# M506C.net
KiCad netlist of a schematic drawn in EAGLE
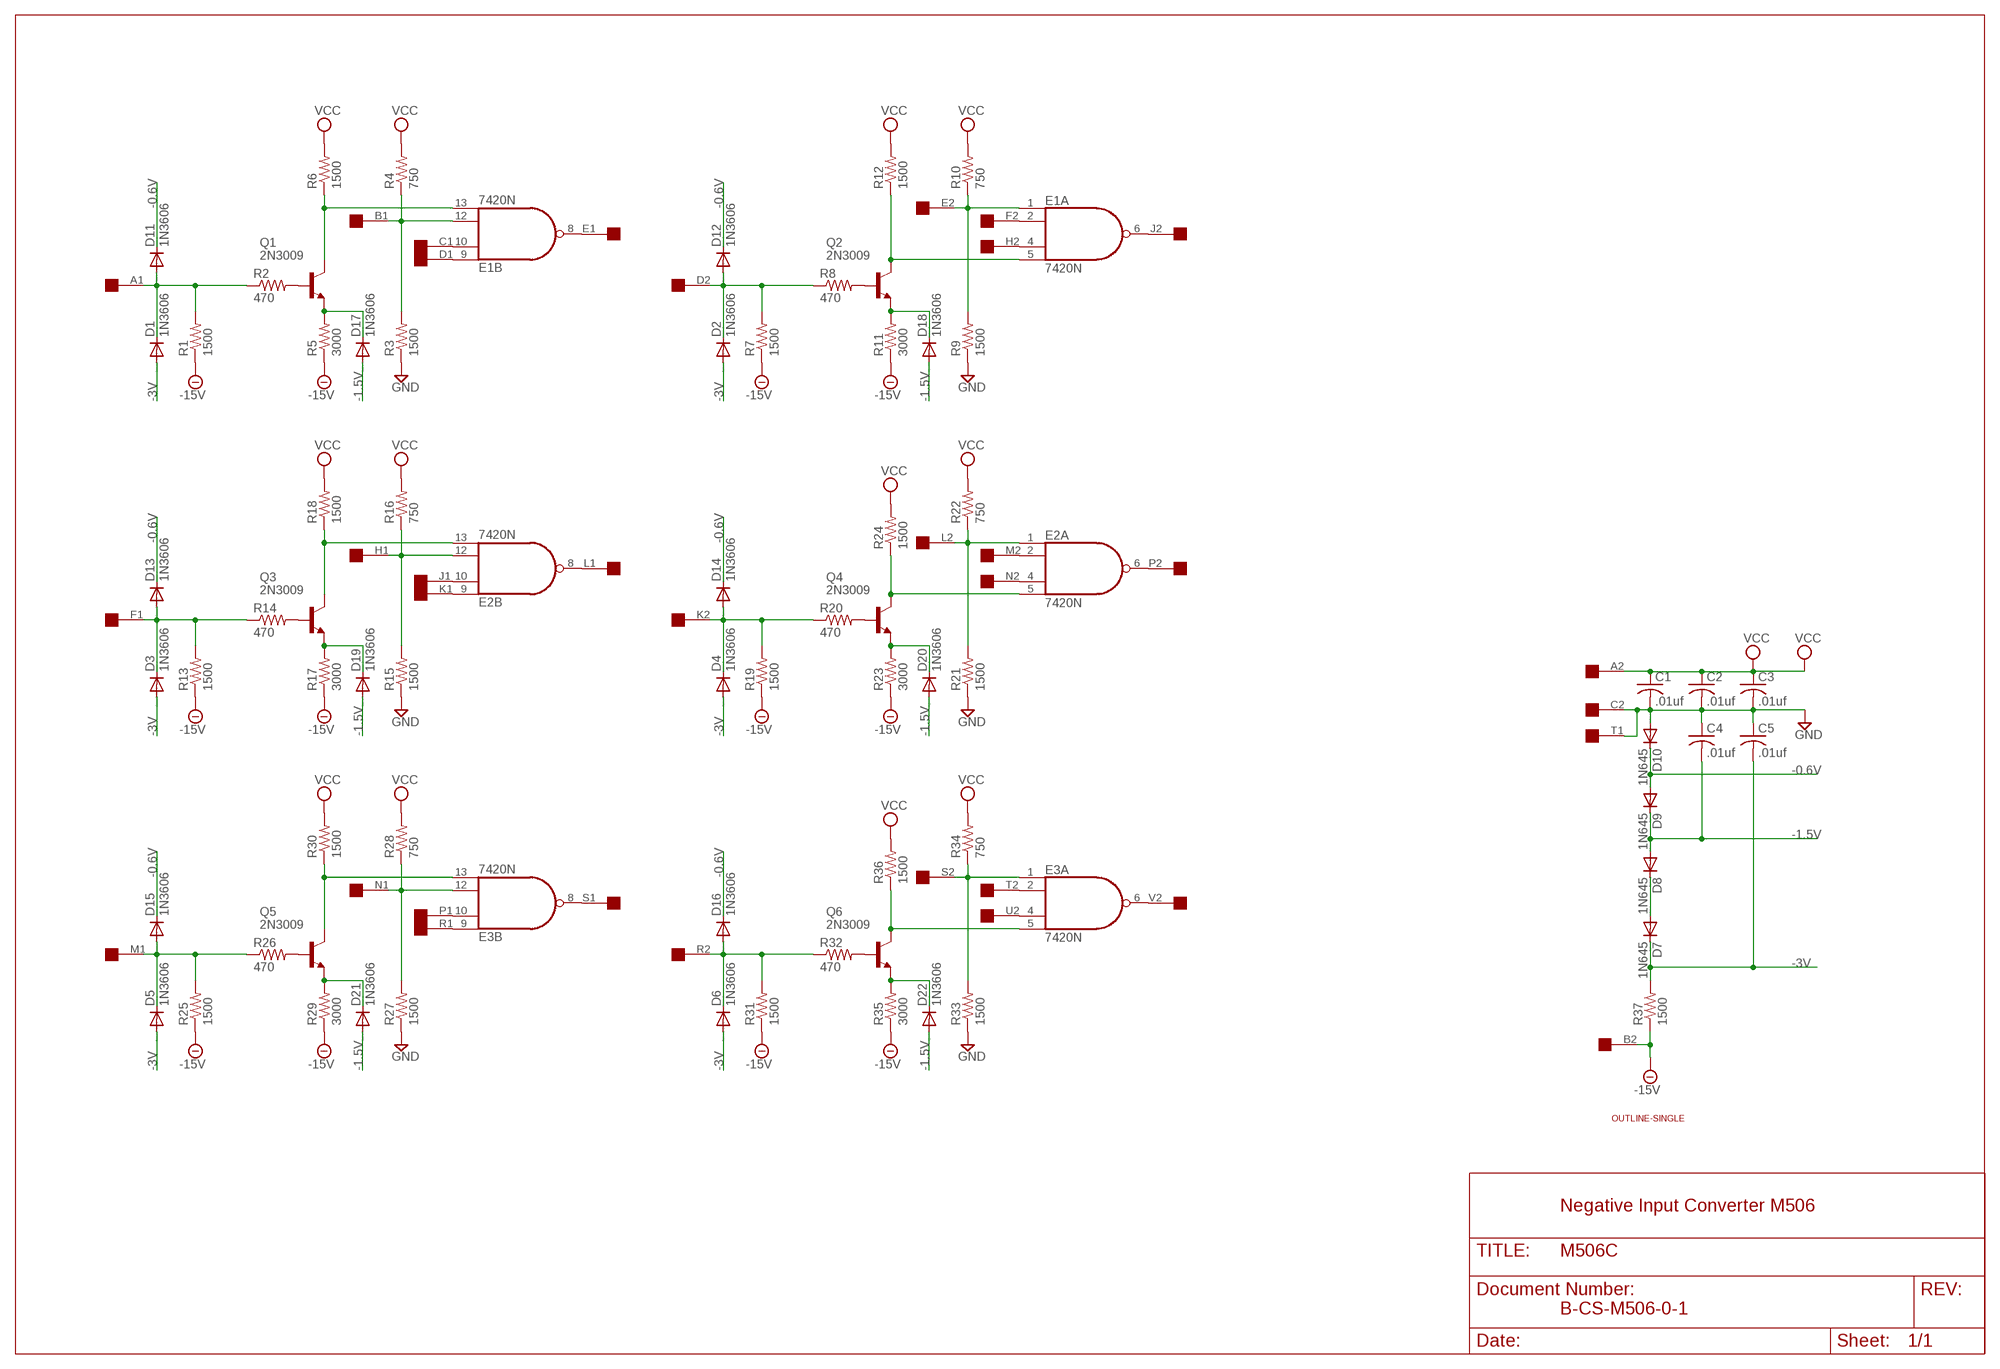
[diagram p0: schematic, sheet 1]

(export (version "E")
  (design (tool "Eeschema 10.0.6"))
  (components
    (comp (ref "C1")
      (value ".01uf")
      (footprint "eagle-import:C050-025X075")
      (libsource (lib "eagle-import") (part "C-US050-025X075"))
    )
    (comp (ref "C2")
      (value ".01uf")
      (footprint "eagle-import:C050-025X075")
      (libsource (lib "eagle-import") (part "C-US050-025X075"))
    )
    (comp (ref "C3")
      (value ".01uf")
      (footprint "eagle-import:C050-025X075")
      (libsource (lib "eagle-import") (part "C-US050-025X075"))
    )
    (comp (ref "C4")
      (value ".01uf")
      (footprint "eagle-import:C050-025X075")
      (libsource (lib "eagle-import") (part "C-US050-025X075"))
    )
    (comp (ref "C5")
      (value ".01uf")
      (footprint "eagle-import:C050-025X075")
      (libsource (lib "eagle-import") (part "C-US050-025X075"))
    )
    (comp (ref "D1")
      (value "1N3606")
      (footprint "eagle-import:DO35-10")
      (libsource (lib "eagle-import") (part "1N4148DO35-10"))
    )
    (comp (ref "D2")
      (value "1N3606")
      (footprint "eagle-import:DO35-10")
      (libsource (lib "eagle-import") (part "1N4148DO35-10"))
    )
    (comp (ref "D3")
      (value "1N3606")
      (footprint "eagle-import:DO35-10")
      (libsource (lib "eagle-import") (part "1N4148DO35-10"))
    )
    (comp (ref "D4")
      (value "1N3606")
      (footprint "eagle-import:DO35-10")
      (libsource (lib "eagle-import") (part "1N4148DO35-10"))
    )
    (comp (ref "D5")
      (value "1N3606")
      (footprint "eagle-import:DO35-10")
      (libsource (lib "eagle-import") (part "1N4148DO35-10"))
    )
    (comp (ref "D6")
      (value "1N3606")
      (footprint "eagle-import:DO35-10")
      (libsource (lib "eagle-import") (part "1N4148DO35-10"))
    )
    (comp (ref "D7")
      (value "1N645")
      (footprint "eagle-import:DO35-10")
      (libsource (lib "eagle-import") (part "1N4148DO35-10"))
    )
    (comp (ref "D8")
      (value "1N645")
      (footprint "eagle-import:DO35-10")
      (libsource (lib "eagle-import") (part "1N4148DO35-10"))
    )
    (comp (ref "D9")
      (value "1N645")
      (footprint "eagle-import:DO35-10")
      (libsource (lib "eagle-import") (part "1N4148DO35-10"))
    )
    (comp (ref "D10")
      (value "1N645")
      (footprint "eagle-import:DO35-10")
      (libsource (lib "eagle-import") (part "1N4148DO35-10"))
    )
    (comp (ref "D11")
      (value "1N3606")
      (footprint "eagle-import:DO35-10")
      (libsource (lib "eagle-import") (part "1N4148DO35-10"))
    )
    (comp (ref "D12")
      (value "1N3606")
      (footprint "eagle-import:DO35-10")
      (libsource (lib "eagle-import") (part "1N4148DO35-10"))
    )
    (comp (ref "D13")
      (value "1N3606")
      (footprint "eagle-import:DO35-10")
      (libsource (lib "eagle-import") (part "1N4148DO35-10"))
    )
    (comp (ref "D14")
      (value "1N3606")
      (footprint "eagle-import:DO35-10")
      (libsource (lib "eagle-import") (part "1N4148DO35-10"))
    )
    (comp (ref "D15")
      (value "1N3606")
      (footprint "eagle-import:DO35-10")
      (libsource (lib "eagle-import") (part "1N4148DO35-10"))
    )
    (comp (ref "D16")
      (value "1N3606")
      (footprint "eagle-import:DO35-10")
      (libsource (lib "eagle-import") (part "1N4148DO35-10"))
    )
    (comp (ref "D17")
      (value "1N3606")
      (footprint "eagle-import:DO35-10")
      (libsource (lib "eagle-import") (part "1N4148DO35-10"))
    )
    (comp (ref "D18")
      (value "1N3606")
      (footprint "eagle-import:DO35-10")
      (libsource (lib "eagle-import") (part "1N4148DO35-10"))
    )
    (comp (ref "D19")
      (value "1N3606")
      (footprint "eagle-import:DO35-10")
      (libsource (lib "eagle-import") (part "1N4148DO35-10"))
    )
    (comp (ref "D20")
      (value "1N3606")
      (footprint "eagle-import:DO35-10")
      (libsource (lib "eagle-import") (part "1N4148DO35-10"))
    )
    (comp (ref "D21")
      (value "1N3606")
      (footprint "eagle-import:DO35-10")
      (libsource (lib "eagle-import") (part "1N4148DO35-10"))
    )
    (comp (ref "D22")
      (value "1N3606")
      (footprint "eagle-import:DO35-10")
      (libsource (lib "eagle-import") (part "1N4148DO35-10"))
    )
    (comp (ref "E1")
      (value "7420N")
      (footprint "eagle-import:DIL14")
      (libsource (lib "eagle-import") (part "7420NS"))
    )
    (comp (ref "E2")
      (value "7420N")
      (footprint "eagle-import:DIL14")
      (libsource (lib "eagle-import") (part "7420NS"))
    )
    (comp (ref "E3")
      (value "7420N")
      (footprint "eagle-import:DIL14")
      (libsource (lib "eagle-import") (part "7420NS"))
    )
    (comp (ref "Q1")
      (value "2N3009")
      (footprint "eagle-import:TO39")
      (libsource (lib "eagle-import") (part "2N3019"))
    )
    (comp (ref "Q2")
      (value "2N3009")
      (footprint "eagle-import:TO39")
      (libsource (lib "eagle-import") (part "2N3019"))
    )
    (comp (ref "Q3")
      (value "2N3009")
      (footprint "eagle-import:TO39")
      (libsource (lib "eagle-import") (part "2N3019"))
    )
    (comp (ref "Q4")
      (value "2N3009")
      (footprint "eagle-import:TO39")
      (libsource (lib "eagle-import") (part "2N3019"))
    )
    (comp (ref "Q5")
      (value "2N3009")
      (footprint "eagle-import:TO39")
      (libsource (lib "eagle-import") (part "2N3019"))
    )
    (comp (ref "Q6")
      (value "2N3009")
      (footprint "eagle-import:TO39")
      (libsource (lib "eagle-import") (part "2N3019"))
    )
    (comp (ref "R1")
      (value "1500")
      (footprint "eagle-import:0207_10")
      (libsource (lib "eagle-import") (part "R-US_0207/10"))
    )
    (comp (ref "R2")
      (value "470")
      (footprint "eagle-import:0207_10")
      (libsource (lib "eagle-import") (part "R-US_0207/10"))
    )
    (comp (ref "R3")
      (value "1500")
      (footprint "eagle-import:0207_10")
      (libsource (lib "eagle-import") (part "R-US_0207/10"))
    )
    (comp (ref "R4")
      (value "750")
      (footprint "eagle-import:0207_10")
      (libsource (lib "eagle-import") (part "R-US_0207/10"))
    )
    (comp (ref "R5")
      (value "3000")
      (footprint "eagle-import:0207_10")
      (libsource (lib "eagle-import") (part "R-US_0207/10"))
    )
    (comp (ref "R6")
      (value "1500")
      (footprint "eagle-import:0207_10")
      (libsource (lib "eagle-import") (part "R-US_0207/10"))
    )
    (comp (ref "R7")
      (value "1500")
      (footprint "eagle-import:0207_10")
      (libsource (lib "eagle-import") (part "R-US_0207/10"))
    )
    (comp (ref "R8")
      (value "470")
      (footprint "eagle-import:0207_10")
      (libsource (lib "eagle-import") (part "R-US_0207/10"))
    )
    (comp (ref "R9")
      (value "1500")
      (footprint "eagle-import:0207_10")
      (libsource (lib "eagle-import") (part "R-US_0207/10"))
    )
    (comp (ref "R10")
      (value "750")
      (footprint "eagle-import:0207_10")
      (libsource (lib "eagle-import") (part "R-US_0207/10"))
    )
    (comp (ref "R11")
      (value "3000")
      (footprint "eagle-import:0207_10")
      (libsource (lib "eagle-import") (part "R-US_0207/10"))
    )
    (comp (ref "R12")
      (value "1500")
      (footprint "eagle-import:0207_10")
      (libsource (lib "eagle-import") (part "R-US_0207/10"))
    )
    (comp (ref "R13")
      (value "1500")
      (footprint "eagle-import:0207_10")
      (libsource (lib "eagle-import") (part "R-US_0207/10"))
    )
    (comp (ref "R14")
      (value "470")
      (footprint "eagle-import:0207_10")
      (libsource (lib "eagle-import") (part "R-US_0207/10"))
    )
    (comp (ref "R15")
      (value "1500")
      (footprint "eagle-import:0207_10")
      (libsource (lib "eagle-import") (part "R-US_0207/10"))
    )
    (comp (ref "R16")
      (value "750")
      (footprint "eagle-import:0207_10")
      (libsource (lib "eagle-import") (part "R-US_0207/10"))
    )
    (comp (ref "R17")
      (value "3000")
      (footprint "eagle-import:0207_10")
      (libsource (lib "eagle-import") (part "R-US_0207/10"))
    )
    (comp (ref "R18")
      (value "1500")
      (footprint "eagle-import:0207_10")
      (libsource (lib "eagle-import") (part "R-US_0207/10"))
    )
    (comp (ref "R19")
      (value "1500")
      (footprint "eagle-import:0207_10")
      (libsource (lib "eagle-import") (part "R-US_0207/10"))
    )
    (comp (ref "R20")
      (value "470")
      (footprint "eagle-import:0207_10")
      (libsource (lib "eagle-import") (part "R-US_0207/10"))
    )
    (comp (ref "R21")
      (value "1500")
      (footprint "eagle-import:0207_10")
      (libsource (lib "eagle-import") (part "R-US_0207/10"))
    )
    (comp (ref "R22")
      (value "750")
      (footprint "eagle-import:0207_10")
      (libsource (lib "eagle-import") (part "R-US_0207/10"))
    )
    (comp (ref "R23")
      (value "3000")
      (footprint "eagle-import:0207_10")
      (libsource (lib "eagle-import") (part "R-US_0207/10"))
    )
    (comp (ref "R24")
      (value "1500")
      (footprint "eagle-import:0207_10")
      (libsource (lib "eagle-import") (part "R-US_0207/10"))
    )
    (comp (ref "R25")
      (value "1500")
      (footprint "eagle-import:0207_10")
      (libsource (lib "eagle-import") (part "R-US_0207/10"))
    )
    (comp (ref "R26")
      (value "470")
      (footprint "eagle-import:0207_10")
      (libsource (lib "eagle-import") (part "R-US_0207/10"))
    )
    (comp (ref "R27")
      (value "1500")
      (footprint "eagle-import:0207_10")
      (libsource (lib "eagle-import") (part "R-US_0207/10"))
    )
    (comp (ref "R28")
      (value "750")
      (footprint "eagle-import:0207_10")
      (libsource (lib "eagle-import") (part "R-US_0207/10"))
    )
    (comp (ref "R29")
      (value "3000")
      (footprint "eagle-import:0207_10")
      (libsource (lib "eagle-import") (part "R-US_0207/10"))
    )
    (comp (ref "R30")
      (value "1500")
      (footprint "eagle-import:0207_10")
      (libsource (lib "eagle-import") (part "R-US_0207/10"))
    )
    (comp (ref "R31")
      (value "1500")
      (footprint "eagle-import:0207_10")
      (libsource (lib "eagle-import") (part "R-US_0207/10"))
    )
    (comp (ref "R32")
      (value "470")
      (footprint "eagle-import:0207_10")
      (libsource (lib "eagle-import") (part "R-US_0207/10"))
    )
    (comp (ref "R33")
      (value "1500")
      (footprint "eagle-import:0207_10")
      (libsource (lib "eagle-import") (part "R-US_0207/10"))
    )
    (comp (ref "R34")
      (value "750")
      (footprint "eagle-import:0207_10")
      (libsource (lib "eagle-import") (part "R-US_0207/10"))
    )
    (comp (ref "R35")
      (value "3000")
      (footprint "eagle-import:0207_10")
      (libsource (lib "eagle-import") (part "R-US_0207/10"))
    )
    (comp (ref "R36")
      (value "1500")
      (footprint "eagle-import:0207_10")
      (libsource (lib "eagle-import") (part "R-US_0207/10"))
    )
    (comp (ref "R37")
      (value "1500")
      (footprint "eagle-import:0207_10")
      (libsource (lib "eagle-import") (part "R-US_0207/10"))
    )
    (comp (ref "U$2")
      (value "SINGLE")
      (footprint "eagle-import:EDGE-CON2")
      (libsource (lib "eagle-import") (part "SINGLE"))
    )
    (comp (ref "U$4")
      (value "OUTLINE-SINGLE")
      (footprint "eagle-import:SINGLE")
      (libsource (lib "eagle-import") (part "OUTLINE-SINGLE"))
    )
  )
  (nets
    (net (code "1") (name "-15V") (class "Default")
      (node (ref "R1") (pin "1") (pinfunction "1_1") (pintype "passive"))
      (node (ref "R11") (pin "1") (pinfunction "1_1") (pintype "passive"))
      (node (ref "R13") (pin "1") (pinfunction "1_1") (pintype "passive"))
      (node (ref "R17") (pin "1") (pinfunction "1_1") (pintype "passive"))
      (node (ref "R19") (pin "1") (pinfunction "1_1") (pintype "passive"))
      (node (ref "R23") (pin "1") (pinfunction "1_1") (pintype "passive"))
      (node (ref "R25") (pin "1") (pinfunction "1_1") (pintype "passive"))
      (node (ref "R29") (pin "1") (pinfunction "1_1") (pintype "passive"))
      (node (ref "R31") (pin "1") (pinfunction "1_1") (pintype "passive"))
      (node (ref "R35") (pin "1") (pinfunction "1_1") (pintype "passive"))
      (node (ref "R37") (pin "1") (pinfunction "1_1") (pintype "passive"))
      (node (ref "R5") (pin "1") (pinfunction "1_1") (pintype "passive"))
      (node (ref "R7") (pin "1") (pinfunction "1_1") (pintype "passive"))
      (node (ref "U$2") (pin "B2") (pinfunction "1_B2") (pintype "bidirectional"))
    )
    (net (code "2") (name "/-0.6V") (class "Default")
      (node (ref "D10") (pin "C") (pinfunction "C_C") (pintype "passive"))
      (node (ref "D11") (pin "C") (pinfunction "C_C") (pintype "passive"))
      (node (ref "D12") (pin "C") (pinfunction "C_C") (pintype "passive"))
      (node (ref "D13") (pin "C") (pinfunction "C_C") (pintype "passive"))
      (node (ref "D14") (pin "C") (pinfunction "C_C") (pintype "passive"))
      (node (ref "D15") (pin "C") (pinfunction "C_C") (pintype "passive"))
      (node (ref "D16") (pin "C") (pinfunction "C_C") (pintype "passive"))
      (node (ref "D9") (pin "A") (pinfunction "A_A") (pintype "passive"))
    )
    (net (code "3") (name "/-1.5V") (class "Default")
      (node (ref "C4") (pin "2") (pinfunction "2_2") (pintype "passive"))
      (node (ref "D17") (pin "A") (pinfunction "A_A") (pintype "passive"))
      (node (ref "D18") (pin "A") (pinfunction "A_A") (pintype "passive"))
      (node (ref "D19") (pin "A") (pinfunction "A_A") (pintype "passive"))
      (node (ref "D20") (pin "A") (pinfunction "A_A") (pintype "passive"))
      (node (ref "D21") (pin "A") (pinfunction "A_A") (pintype "passive"))
      (node (ref "D22") (pin "A") (pinfunction "A_A") (pintype "passive"))
      (node (ref "D8") (pin "A") (pinfunction "A_A") (pintype "passive"))
      (node (ref "D9") (pin "C") (pinfunction "C_C") (pintype "passive"))
    )
    (net (code "4") (name "/-3V") (class "Default")
      (node (ref "C5") (pin "2") (pinfunction "2_2") (pintype "passive"))
      (node (ref "D1") (pin "A") (pinfunction "A_A") (pintype "passive"))
      (node (ref "D2") (pin "A") (pinfunction "A_A") (pintype "passive"))
      (node (ref "D3") (pin "A") (pinfunction "A_A") (pintype "passive"))
      (node (ref "D4") (pin "A") (pinfunction "A_A") (pintype "passive"))
      (node (ref "D5") (pin "A") (pinfunction "A_A") (pintype "passive"))
      (node (ref "D6") (pin "A") (pinfunction "A_A") (pintype "passive"))
      (node (ref "D7") (pin "C") (pinfunction "C_C") (pintype "passive"))
      (node (ref "R37") (pin "2") (pinfunction "2_2") (pintype "passive"))
    )
    (net (code "5") (name "GND") (class "Default")
      (node (ref "C1") (pin "2") (pinfunction "2_2") (pintype "passive"))
      (node (ref "C2") (pin "2") (pinfunction "2_2") (pintype "passive"))
      (node (ref "C3") (pin "2") (pinfunction "2_2") (pintype "passive"))
      (node (ref "C4") (pin "1") (pinfunction "1_1") (pintype "passive"))
      (node (ref "C5") (pin "1") (pinfunction "1_1") (pintype "passive"))
      (node (ref "D10") (pin "A") (pinfunction "A_A") (pintype "passive"))
      (node (ref "R15") (pin "1") (pinfunction "1_1") (pintype "passive"))
      (node (ref "R21") (pin "1") (pinfunction "1_1") (pintype "passive"))
      (node (ref "R27") (pin "1") (pinfunction "1_1") (pintype "passive"))
      (node (ref "R3") (pin "1") (pinfunction "1_1") (pintype "passive"))
      (node (ref "R33") (pin "1") (pinfunction "1_1") (pintype "passive"))
      (node (ref "R9") (pin "1") (pinfunction "1_1") (pintype "passive"))
      (node (ref "U$2") (pin "C2") (pinfunction "1_C2") (pintype "bidirectional"))
      (node (ref "U$2") (pin "T1") (pinfunction "1_T1") (pintype "bidirectional"))
    )
    (net (code "6") (name "Net-(D7-PadA)") (class "Default")
      (node (ref "D7") (pin "A") (pinfunction "A_A") (pintype "passive"))
      (node (ref "D8") (pin "C") (pinfunction "C_C") (pintype "passive"))
    )
    (net (code "7") (name "Net-(E1A-I0)") (class "Default")
      (node (ref "E1") (pin "1") (pinfunction "I0_1") (pintype "input"))
      (node (ref "R10") (pin "1") (pinfunction "1_1") (pintype "passive"))
      (node (ref "R9") (pin "2") (pinfunction "2_2") (pintype "passive"))
      (node (ref "U$2") (pin "E2") (pinfunction "1_E2") (pintype "bidirectional"))
    )
    (net (code "8") (name "Net-(E1A-I1)") (class "Default")
      (node (ref "E1") (pin "2") (pinfunction "I1_2") (pintype "input"))
      (node (ref "U$2") (pin "F2") (pinfunction "1_F2") (pintype "bidirectional"))
    )
    (net (code "9") (name "Net-(E1A-I2)") (class "Default")
      (node (ref "E1") (pin "4") (pinfunction "I2_4") (pintype "input"))
      (node (ref "U$2") (pin "H2") (pinfunction "1_H2") (pintype "bidirectional"))
    )
    (net (code "10") (name "Net-(E1A-I3)") (class "Default")
      (node (ref "E1") (pin "5") (pinfunction "I3_5") (pintype "input"))
      (node (ref "Q2") (pin "3") (pinfunction "C_3") (pintype "passive"))
      (node (ref "R12") (pin "1") (pinfunction "1_1") (pintype "passive"))
    )
    (net (code "11") (name "Net-(E1A-O)") (class "Default")
      (node (ref "E1") (pin "6") (pinfunction "O_6") (pintype "output"))
      (node (ref "U$2") (pin "J2") (pinfunction "1_J2") (pintype "bidirectional"))
    )
    (net (code "12") (name "Net-(E1B-I0)") (class "Default")
      (node (ref "E1") (pin "9") (pinfunction "I0_9") (pintype "input"))
      (node (ref "U$2") (pin "D1") (pinfunction "1_D1") (pintype "bidirectional"))
    )
    (net (code "13") (name "Net-(E1B-I1)") (class "Default")
      (node (ref "E1") (pin "10") (pinfunction "I1_10") (pintype "input"))
      (node (ref "U$2") (pin "C1") (pinfunction "1_C1") (pintype "bidirectional"))
    )
    (net (code "14") (name "Net-(E1B-I2)") (class "Default")
      (node (ref "E1") (pin "12") (pinfunction "I2_12") (pintype "input"))
      (node (ref "R3") (pin "2") (pinfunction "2_2") (pintype "passive"))
      (node (ref "R4") (pin "1") (pinfunction "1_1") (pintype "passive"))
      (node (ref "U$2") (pin "B1") (pinfunction "1_B1") (pintype "bidirectional"))
    )
    (net (code "15") (name "Net-(E1B-I3)") (class "Default")
      (node (ref "E1") (pin "13") (pinfunction "I3_13") (pintype "input"))
      (node (ref "Q1") (pin "3") (pinfunction "C_3") (pintype "passive"))
      (node (ref "R6") (pin "1") (pinfunction "1_1") (pintype "passive"))
    )
    (net (code "16") (name "Net-(E1B-O)") (class "Default")
      (node (ref "E1") (pin "8") (pinfunction "O_8") (pintype "output"))
      (node (ref "U$2") (pin "E1") (pinfunction "1_E1") (pintype "bidirectional"))
    )
    (net (code "17") (name "Net-(E2A-I0)") (class "Default")
      (node (ref "E2") (pin "1") (pinfunction "I0_1") (pintype "input"))
      (node (ref "R21") (pin "2") (pinfunction "2_2") (pintype "passive"))
      (node (ref "R22") (pin "1") (pinfunction "1_1") (pintype "passive"))
      (node (ref "U$2") (pin "L2") (pinfunction "1_L2") (pintype "bidirectional"))
    )
    (net (code "18") (name "Net-(E2A-I1)") (class "Default")
      (node (ref "E2") (pin "2") (pinfunction "I1_2") (pintype "input"))
      (node (ref "U$2") (pin "M2") (pinfunction "1_M2") (pintype "bidirectional"))
    )
    (net (code "19") (name "Net-(E2A-I2)") (class "Default")
      (node (ref "E2") (pin "4") (pinfunction "I2_4") (pintype "input"))
      (node (ref "U$2") (pin "N2") (pinfunction "1_N2") (pintype "bidirectional"))
    )
    (net (code "20") (name "Net-(E2A-I3)") (class "Default")
      (node (ref "E2") (pin "5") (pinfunction "I3_5") (pintype "input"))
      (node (ref "Q4") (pin "3") (pinfunction "C_3") (pintype "passive"))
      (node (ref "R24") (pin "1") (pinfunction "1_1") (pintype "passive"))
    )
    (net (code "21") (name "Net-(E2A-O)") (class "Default")
      (node (ref "E2") (pin "6") (pinfunction "O_6") (pintype "output"))
      (node (ref "U$2") (pin "P2") (pinfunction "1_P2") (pintype "bidirectional"))
    )
    (net (code "22") (name "Net-(E2B-I0)") (class "Default")
      (node (ref "E2") (pin "9") (pinfunction "I0_9") (pintype "input"))
      (node (ref "U$2") (pin "K1") (pinfunction "1_K1") (pintype "bidirectional"))
    )
    (net (code "23") (name "Net-(E2B-I1)") (class "Default")
      (node (ref "E2") (pin "10") (pinfunction "I1_10") (pintype "input"))
      (node (ref "U$2") (pin "J1") (pinfunction "1_J1") (pintype "bidirectional"))
    )
    (net (code "24") (name "Net-(E2B-I2)") (class "Default")
      (node (ref "E2") (pin "12") (pinfunction "I2_12") (pintype "input"))
      (node (ref "R15") (pin "2") (pinfunction "2_2") (pintype "passive"))
      (node (ref "R16") (pin "1") (pinfunction "1_1") (pintype "passive"))
      (node (ref "U$2") (pin "H1") (pinfunction "1_H1") (pintype "bidirectional"))
    )
    (net (code "25") (name "Net-(E2B-I3)") (class "Default")
      (node (ref "E2") (pin "13") (pinfunction "I3_13") (pintype "input"))
      (node (ref "Q3") (pin "3") (pinfunction "C_3") (pintype "passive"))
      (node (ref "R18") (pin "1") (pinfunction "1_1") (pintype "passive"))
    )
    (net (code "26") (name "Net-(E2B-O)") (class "Default")
      (node (ref "E2") (pin "8") (pinfunction "O_8") (pintype "output"))
      (node (ref "U$2") (pin "L1") (pinfunction "1_L1") (pintype "bidirectional"))
    )
    (net (code "27") (name "Net-(E3A-I0)") (class "Default")
      (node (ref "E3") (pin "1") (pinfunction "I0_1") (pintype "input"))
      (node (ref "R33") (pin "2") (pinfunction "2_2") (pintype "passive"))
      (node (ref "R34") (pin "1") (pinfunction "1_1") (pintype "passive"))
      (node (ref "U$2") (pin "S2") (pinfunction "1_S2") (pintype "bidirectional"))
    )
    (net (code "28") (name "Net-(E3A-I1)") (class "Default")
      (node (ref "E3") (pin "2") (pinfunction "I1_2") (pintype "input"))
      (node (ref "U$2") (pin "T2") (pinfunction "1_T2") (pintype "bidirectional"))
    )
    (net (code "29") (name "Net-(E3A-I2)") (class "Default")
      (node (ref "E3") (pin "4") (pinfunction "I2_4") (pintype "input"))
      (node (ref "U$2") (pin "U2") (pinfunction "1_U2") (pintype "bidirectional"))
    )
    (net (code "30") (name "Net-(E3A-I3)") (class "Default")
      (node (ref "E3") (pin "5") (pinfunction "I3_5") (pintype "input"))
      (node (ref "Q6") (pin "3") (pinfunction "C_3") (pintype "passive"))
      (node (ref "R36") (pin "1") (pinfunction "1_1") (pintype "passive"))
    )
    (net (code "31") (name "Net-(E3A-O)") (class "Default")
      (node (ref "E3") (pin "6") (pinfunction "O_6") (pintype "output"))
      (node (ref "U$2") (pin "V2") (pinfunction "1_V2") (pintype "bidirectional"))
    )
    (net (code "32") (name "Net-(E3B-I0)") (class "Default")
      (node (ref "E3") (pin "9") (pinfunction "I0_9") (pintype "input"))
      (node (ref "U$2") (pin "R1") (pinfunction "1_R1") (pintype "bidirectional"))
    )
    (net (code "33") (name "Net-(E3B-I1)") (class "Default")
      (node (ref "E3") (pin "10") (pinfunction "I1_10") (pintype "input"))
      (node (ref "U$2") (pin "P1") (pinfunction "1_P1") (pintype "bidirectional"))
    )
    (net (code "34") (name "Net-(E3B-I2)") (class "Default")
      (node (ref "E3") (pin "12") (pinfunction "I2_12") (pintype "input"))
      (node (ref "R27") (pin "2") (pinfunction "2_2") (pintype "passive"))
      (node (ref "R28") (pin "1") (pinfunction "1_1") (pintype "passive"))
      (node (ref "U$2") (pin "N1") (pinfunction "1_N1") (pintype "bidirectional"))
    )
    (net (code "35") (name "Net-(E3B-I3)") (class "Default")
      (node (ref "E3") (pin "13") (pinfunction "I3_13") (pintype "input"))
      (node (ref "Q5") (pin "3") (pinfunction "C_3") (pintype "passive"))
      (node (ref "R30") (pin "1") (pinfunction "1_1") (pintype "passive"))
    )
    (net (code "36") (name "Net-(E3B-O)") (class "Default")
      (node (ref "E3") (pin "8") (pinfunction "O_8") (pintype "output"))
      (node (ref "U$2") (pin "S1") (pinfunction "1_S1") (pintype "bidirectional"))
    )
    (net (code "37") (name "Net-(Q1-B)") (class "Default")
      (node (ref "Q1") (pin "2") (pinfunction "B_2") (pintype "passive"))
      (node (ref "R2") (pin "2") (pinfunction "2_2") (pintype "passive"))
    )
    (net (code "38") (name "Net-(Q1-E)") (class "Default")
      (node (ref "D17") (pin "C") (pinfunction "C_C") (pintype "passive"))
      (node (ref "Q1") (pin "1") (pinfunction "E_1") (pintype "passive"))
      (node (ref "R5") (pin "2") (pinfunction "2_2") (pintype "passive"))
    )
    (net (code "39") (name "Net-(Q2-B)") (class "Default")
      (node (ref "Q2") (pin "2") (pinfunction "B_2") (pintype "passive"))
      (node (ref "R8") (pin "2") (pinfunction "2_2") (pintype "passive"))
    )
    (net (code "40") (name "Net-(Q2-E)") (class "Default")
      (node (ref "D18") (pin "C") (pinfunction "C_C") (pintype "passive"))
      (node (ref "Q2") (pin "1") (pinfunction "E_1") (pintype "passive"))
      (node (ref "R11") (pin "2") (pinfunction "2_2") (pintype "passive"))
    )
    (net (code "41") (name "Net-(Q3-B)") (class "Default")
      (node (ref "Q3") (pin "2") (pinfunction "B_2") (pintype "passive"))
      (node (ref "R14") (pin "2") (pinfunction "2_2") (pintype "passive"))
    )
    (net (code "42") (name "Net-(Q3-E)") (class "Default")
      (node (ref "D19") (pin "C") (pinfunction "C_C") (pintype "passive"))
      (node (ref "Q3") (pin "1") (pinfunction "E_1") (pintype "passive"))
      (node (ref "R17") (pin "2") (pinfunction "2_2") (pintype "passive"))
    )
    (net (code "43") (name "Net-(Q4-B)") (class "Default")
      (node (ref "Q4") (pin "2") (pinfunction "B_2") (pintype "passive"))
      (node (ref "R20") (pin "2") (pinfunction "2_2") (pintype "passive"))
    )
    (net (code "44") (name "Net-(Q4-E)") (class "Default")
      (node (ref "D20") (pin "C") (pinfunction "C_C") (pintype "passive"))
      (node (ref "Q4") (pin "1") (pinfunction "E_1") (pintype "passive"))
      (node (ref "R23") (pin "2") (pinfunction "2_2") (pintype "passive"))
    )
    (net (code "45") (name "Net-(Q5-B)") (class "Default")
      (node (ref "Q5") (pin "2") (pinfunction "B_2") (pintype "passive"))
      (node (ref "R26") (pin "2") (pinfunction "2_2") (pintype "passive"))
    )
    (net (code "46") (name "Net-(Q5-E)") (class "Default")
      (node (ref "D21") (pin "C") (pinfunction "C_C") (pintype "passive"))
      (node (ref "Q5") (pin "1") (pinfunction "E_1") (pintype "passive"))
      (node (ref "R29") (pin "2") (pinfunction "2_2") (pintype "passive"))
    )
    (net (code "47") (name "Net-(Q6-B)") (class "Default")
      (node (ref "Q6") (pin "2") (pinfunction "B_2") (pintype "passive"))
      (node (ref "R32") (pin "2") (pinfunction "2_2") (pintype "passive"))
    )
    (net (code "48") (name "Net-(Q6-E)") (class "Default")
      (node (ref "D22") (pin "C") (pinfunction "C_C") (pintype "passive"))
      (node (ref "Q6") (pin "1") (pinfunction "E_1") (pintype "passive"))
      (node (ref "R35") (pin "2") (pinfunction "2_2") (pintype "passive"))
    )
    (net (code "49") (name "Net-(U$2A-1)") (class "Default")
      (node (ref "D1") (pin "C") (pinfunction "C_C") (pintype "passive"))
      (node (ref "D11") (pin "A") (pinfunction "A_A") (pintype "passive"))
      (node (ref "R1") (pin "2") (pinfunction "2_2") (pintype "passive"))
      (node (ref "R2") (pin "1") (pinfunction "1_1") (pintype "passive"))
      (node (ref "U$2") (pin "A1") (pinfunction "1_A1") (pintype "bidirectional"))
    )
    (net (code "50") (name "Net-(U$2AB-1)") (class "Default")
      (node (ref "D16") (pin "A") (pinfunction "A_A") (pintype "passive"))
      (node (ref "D6") (pin "C") (pinfunction "C_C") (pintype "passive"))
      (node (ref "R31") (pin "2") (pinfunction "2_2") (pintype "passive"))
      (node (ref "R32") (pin "1") (pinfunction "1_1") (pintype "passive"))
      (node (ref "U$2") (pin "R2") (pinfunction "1_R2") (pintype "bidirectional"))
    )
    (net (code "51") (name "Net-(U$2H-1)") (class "Default")
      (node (ref "D12") (pin "A") (pinfunction "A_A") (pintype "passive"))
      (node (ref "D2") (pin "C") (pinfunction "C_C") (pintype "passive"))
      (node (ref "R7") (pin "2") (pinfunction "2_2") (pintype "passive"))
      (node (ref "R8") (pin "1") (pinfunction "1_1") (pintype "passive"))
      (node (ref "U$2") (pin "D2") (pinfunction "1_D2") (pintype "bidirectional"))
    )
    (net (code "52") (name "Net-(U$2K-1)") (class "Default")
      (node (ref "D13") (pin "A") (pinfunction "A_A") (pintype "passive"))
      (node (ref "D3") (pin "C") (pinfunction "C_C") (pintype "passive"))
      (node (ref "R13") (pin "2") (pinfunction "2_2") (pintype "passive"))
      (node (ref "R14") (pin "1") (pinfunction "1_1") (pintype "passive"))
      (node (ref "U$2") (pin "F1") (pinfunction "1_F1") (pintype "bidirectional"))
    )
    (net (code "53") (name "Net-(U$2R-1)") (class "Default")
      (node (ref "D14") (pin "A") (pinfunction "A_A") (pintype "passive"))
      (node (ref "D4") (pin "C") (pinfunction "C_C") (pintype "passive"))
      (node (ref "R19") (pin "2") (pinfunction "2_2") (pintype "passive"))
      (node (ref "R20") (pin "1") (pinfunction "1_1") (pintype "passive"))
      (node (ref "U$2") (pin "K2") (pinfunction "1_K2") (pintype "bidirectional"))
    )
    (net (code "54") (name "Net-(U$2U-1)") (class "Default")
      (node (ref "D15") (pin "A") (pinfunction "A_A") (pintype "passive"))
      (node (ref "D5") (pin "C") (pinfunction "C_C") (pintype "passive"))
      (node (ref "R25") (pin "2") (pinfunction "2_2") (pintype "passive"))
      (node (ref "R26") (pin "1") (pinfunction "1_1") (pintype "passive"))
      (node (ref "U$2") (pin "M1") (pinfunction "1_M1") (pintype "bidirectional"))
    )
    (net (code "55") (name "VCC") (class "Default")
      (node (ref "C1") (pin "1") (pinfunction "1_1") (pintype "passive"))
      (node (ref "C2") (pin "1") (pinfunction "1_1") (pintype "passive"))
      (node (ref "C3") (pin "1") (pinfunction "1_1") (pintype "passive"))
      (node (ref "R10") (pin "2") (pinfunction "2_2") (pintype "passive"))
      (node (ref "R12") (pin "2") (pinfunction "2_2") (pintype "passive"))
      (node (ref "R16") (pin "2") (pinfunction "2_2") (pintype "passive"))
      (node (ref "R18") (pin "2") (pinfunction "2_2") (pintype "passive"))
      (node (ref "R22") (pin "2") (pinfunction "2_2") (pintype "passive"))
      (node (ref "R24") (pin "2") (pinfunction "2_2") (pintype "passive"))
      (node (ref "R28") (pin "2") (pinfunction "2_2") (pintype "passive"))
      (node (ref "R30") (pin "2") (pinfunction "2_2") (pintype "passive"))
      (node (ref "R34") (pin "2") (pinfunction "2_2") (pintype "passive"))
      (node (ref "R36") (pin "2") (pinfunction "2_2") (pintype "passive"))
      (node (ref "R4") (pin "2") (pinfunction "2_2") (pintype "passive"))
      (node (ref "R6") (pin "2") (pinfunction "2_2") (pintype "passive"))
      (node (ref "U$2") (pin "A2") (pinfunction "1_A2") (pintype "bidirectional"))
    )
  )
)
